# audio_dsp.net
KiCad netlist of a schematic drawn in Altium Designer
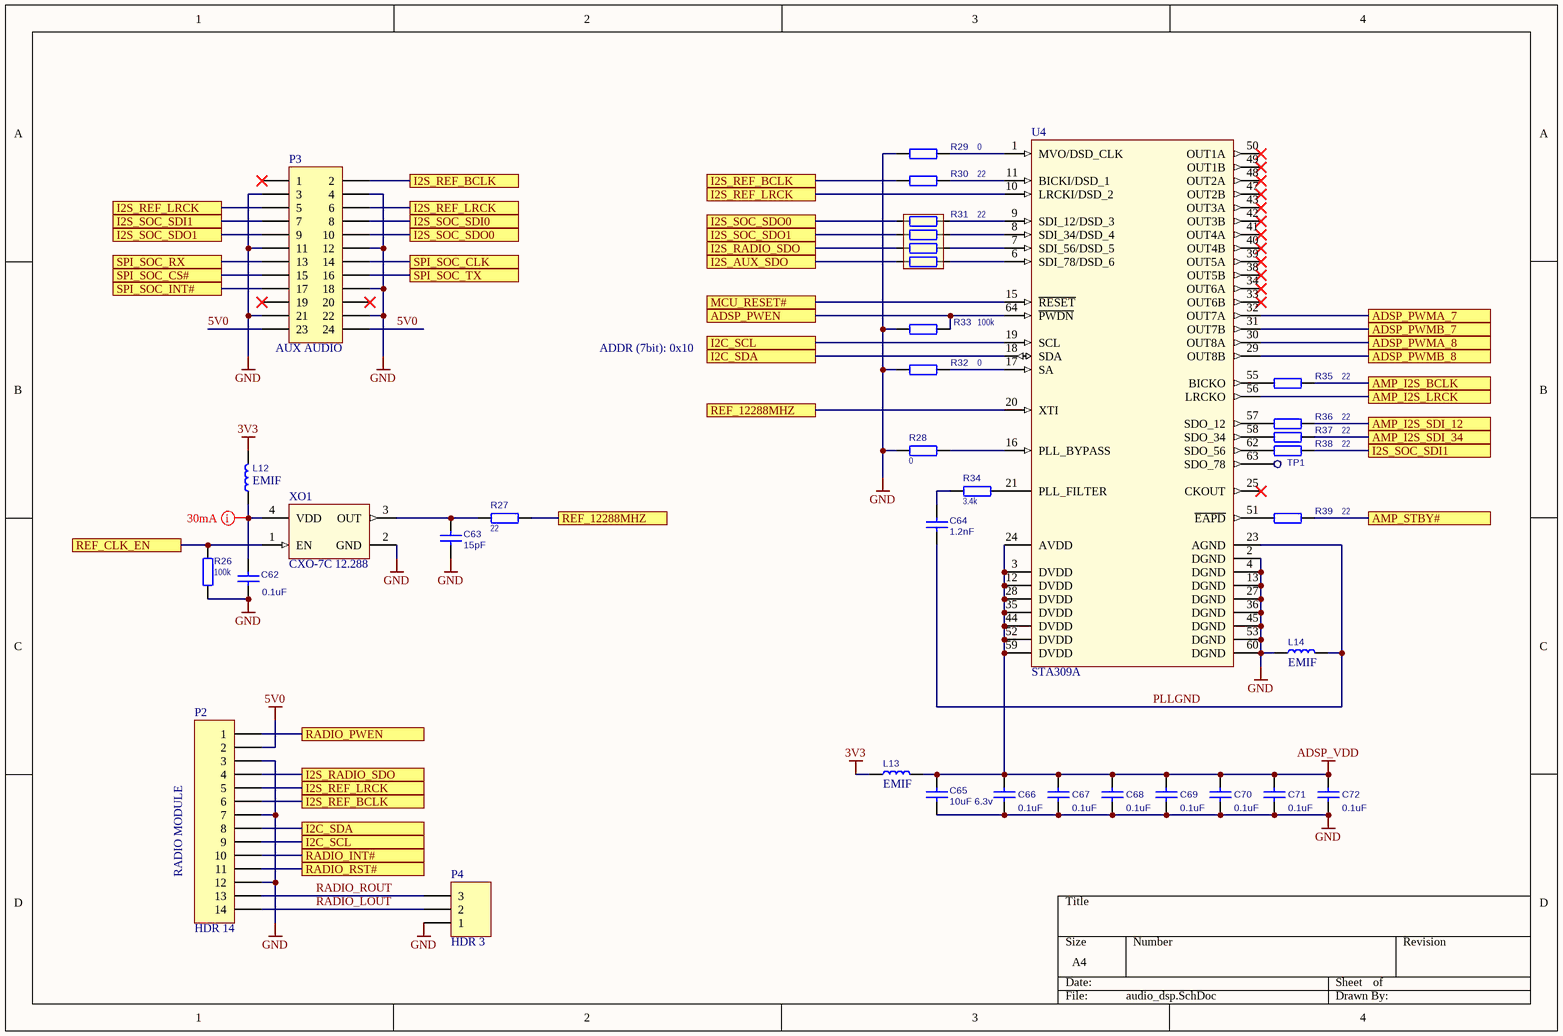
[diagram p0: audio_dsp.SchDoc]

(export (version "E")
  (design (tool "Eeschema 10.0.6"))
  (components
    (comp (ref "C62")
      (value "0.1uF")
      (footprint "Capacitors:C0603")
      (description "CAP_NPOL")
      (fields (field (name "Comment") "CC0603KRX7R9BB104"))
      (libsource (lib "capacitors") (part "CAP_NPOL"))
    )
    (comp (ref "C63")
      (value "15pF")
      (footprint "C0603")
      (description "CAP_NPOL")
      (fields (field (name "Comment") "CC0603GRNPO9BN150"))
      (libsource (lib "capacitors") (part "CAP_NPOL"))
    )
    (comp (ref "C64")
      (value "1.2nF")
      (footprint "Capacitors:C0603")
      (description "CAP_NPOL")
      (fields (field (name "Comment") "GRM1885C1H122JA01D"))
      (libsource (lib "capacitors") (part "CAP_NPOL"))
    )
    (comp (ref "C65")
      (value "10uF 6.3v")
      (footprint "Capacitors:C0603")
      (description "CAP_NPOL")
      (fields (field (name "Comment") "CC0603MRX5R5BB106"))
      (libsource (lib "capacitors") (part "CAP_NPOL"))
    )
    (comp (ref "C66")
      (value "0.1uF")
      (footprint "Capacitors:C0603")
      (description "CAP_NPOL")
      (fields (field (name "Comment") "CC0603KRX7R9BB104"))
      (libsource (lib "capacitors") (part "CAP_NPOL"))
    )
    (comp (ref "C67")
      (value "0.1uF")
      (footprint "Capacitors:C0603")
      (description "CAP_NPOL")
      (fields (field (name "Comment") "CC0603KRX7R9BB104"))
      (libsource (lib "capacitors") (part "CAP_NPOL"))
    )
    (comp (ref "C68")
      (value "0.1uF")
      (footprint "Capacitors:C0603")
      (description "CAP_NPOL")
      (fields (field (name "Comment") "CC0603KRX7R9BB104"))
      (libsource (lib "capacitors") (part "CAP_NPOL"))
    )
    (comp (ref "C69")
      (value "0.1uF")
      (footprint "Capacitors:C0603")
      (description "CAP_NPOL")
      (fields (field (name "Comment") "CC0603KRX7R9BB104"))
      (libsource (lib "capacitors") (part "CAP_NPOL"))
    )
    (comp (ref "C70")
      (value "0.1uF")
      (footprint "Capacitors:C0603")
      (description "CAP_NPOL")
      (fields (field (name "Comment") "CC0603KRX7R9BB104"))
      (libsource (lib "capacitors") (part "CAP_NPOL"))
    )
    (comp (ref "C71")
      (value "0.1uF")
      (footprint "Capacitors:C0603")
      (description "CAP_NPOL")
      (fields (field (name "Comment") "CC0603KRX7R9BB104"))
      (libsource (lib "capacitors") (part "CAP_NPOL"))
    )
    (comp (ref "C72")
      (value "0.1uF")
      (footprint "Capacitors:C0603")
      (description "CAP_NPOL")
      (fields (field (name "Comment") "CC0603KRX7R9BB104"))
      (libsource (lib "capacitors") (part "CAP_NPOL"))
    )
    (comp (ref "L12")
      (value "EMIF")
      (footprint "IND0603")
      (description "IND_WO_IRON")
      (fields (field (name "Comment") "BLM18AG102SN1D"))
      (libsource (lib "inductors") (part "IND_WO_IRON"))
    )
    (comp (ref "L13")
      (value "EMIF")
      (footprint "IND0603")
      (description "IND_WO_IRON")
      (fields (field (name "Comment") "BLM18AG102SN1D"))
      (libsource (lib "inductors") (part "IND_WO_IRON"))
    )
    (comp (ref "L14")
      (value "EMIF")
      (footprint "IND0603")
      (description "IND_WO_IRON")
      (fields (field (name "Comment") "BLM18AG102SN1D"))
      (libsource (lib "inductors") (part "IND_WO_IRON"))
    )
    (comp (ref "P2")
      (value "HDR 14")
      (footprint "PLS-14")
      (description "Header, 14-Pin")
      (fields (field (name "PUBLISHER") "Altium Limited"))
      (libsource (lib "HDR") (part "HDR 14"))
    )
    (comp (ref "P3")
      (value "AUX AUDIO")
      (footprint "PLD-12")
      (description "Header, 12-Pin, Dual row")
      (fields (field (name "PUBLISHER") "Altium Limited"))
      (libsource (lib "HDR") (part "HDR 12X2"))
    )
    (comp (ref "P4")
      (value "HDR 3")
      (footprint "PLS-3")
      (description "Header, 3-Pin")
      (fields (field (name "PUBLISHER") "Altium Limited"))
      (libsource (lib "HDR") (part "HDR 3"))
    )
    (comp (ref "R26")
      (value "100k")
      (footprint "R0603")
      (description "RES")
      (fields (field (name "Comment") "47k"))
      (libsource (lib "resistors") (part "RESISTOR"))
    )
    (comp (ref "R27")
      (value "22")
      (footprint "R0603")
      (description "RES")
      (libsource (lib "resistors") (part "RESISTOR"))
    )
    (comp (ref "R28")
      (value "0")
      (footprint "R0603")
      (description "RES")
      (libsource (lib "resistors") (part "RESISTOR"))
    )
    (comp (ref "R29")
      (value "0")
      (footprint "R0603")
      (description "RES")
      (libsource (lib "resistors") (part "RESISTOR"))
    )
    (comp (ref "R30")
      (value "22")
      (footprint "R0603")
      (description "RES")
      (libsource (lib "resistors") (part "RESISTOR"))
    )
    (comp (ref "R31")
      (value "22")
      (footprint "Resistors:R0804X4")
      (description "ARRAY")
      (fields (field (name "Comment") "TC124-JR-0722RL"))
      (libsource (lib "resistors") (part "ARRAY"))
    )
    (comp (ref "R32")
      (value "0")
      (footprint "R0603")
      (description "RES")
      (libsource (lib "resistors") (part "RESISTOR"))
    )
    (comp (ref "R33")
      (value "100k")
      (footprint "R0603")
      (description "RES")
      (libsource (lib "resistors") (part "RESISTOR"))
    )
    (comp (ref "R34")
      (value "3.4k")
      (footprint "R0603")
      (description "RES")
      (libsource (lib "resistors") (part "RESISTOR"))
    )
    (comp (ref "R35")
      (value "22")
      (footprint "R0603")
      (description "RES")
      (libsource (lib "resistors") (part "RESISTOR"))
    )
    (comp (ref "R36")
      (value "22")
      (footprint "R0603")
      (description "RES")
      (libsource (lib "resistors") (part "RESISTOR"))
    )
    (comp (ref "R37")
      (value "22")
      (footprint "R0603")
      (description "RES")
      (libsource (lib "resistors") (part "RESISTOR"))
    )
    (comp (ref "R38")
      (value "22")
      (footprint "R0603")
      (description "RES")
      (libsource (lib "resistors") (part "RESISTOR"))
    )
    (comp (ref "R39")
      (value "22")
      (footprint "R0603")
      (description "RES")
      (libsource (lib "resistors") (part "RESISTOR"))
    )
    (comp (ref "TP1")
      (value "TEST-POINT")
      (footprint "PAD")
      (description "PCB terminal block")
      (libsource (lib "TestPoint") (part "TEST-POINT"))
    )
    (comp (ref "U4")
      (value "STA309A")
      (footprint "PM064_N")
      (description "Multi-channel digital audio processor with DDX®")
      (libsource (lib "STA309A") (part "STA309A"))
    )
    (comp (ref "XO1") (value "CXO-7C 12.288") (footprint "CXO-5032") (libsource (lib "xtal") (part "CXO-7C")))
  )
  (nets
    (net (code "1") (name "/ADSP_PWEN") (class "Default")
      (node (ref "R33") (pin "1") (pinfunction "1_1") (pintype "passive"))
      (node (ref "U4") (pin "64") (pinfunction "~{PWDN}_64") (pintype "input"))
    )
    (net (code "2") (name "/ADSP_PWMA_7") (class "Default")
      (node (ref "U4") (pin "32") (pinfunction "OUT7A_32") (pintype "output"))
    )
    (net (code "3") (name "/ADSP_PWMA_8") (class "Default")
      (node (ref "U4") (pin "30") (pinfunction "OUT8A_30") (pintype "output"))
    )
    (net (code "4") (name "/ADSP_PWMB_7") (class "Default")
      (node (ref "U4") (pin "31") (pinfunction "OUT7B_31") (pintype "output"))
    )
    (net (code "5") (name "/ADSP_PWMB_8") (class "Default")
      (node (ref "U4") (pin "29") (pinfunction "OUT8B_29") (pintype "output"))
    )
    (net (code "6") (name "/AMP_I2S_BCLK") (class "Default")
      (node (ref "R35") (pin "2") (pinfunction "2_2") (pintype "passive"))
    )
    (net (code "7") (name "/AMP_I2S_LRCK") (class "Default")
      (node (ref "U4") (pin "56") (pinfunction "LRCKO_56") (pintype "output"))
    )
    (net (code "8") (name "/AMP_I2S_SDI_12") (class "Default")
      (node (ref "R36") (pin "2") (pinfunction "2_2") (pintype "passive"))
    )
    (net (code "9") (name "/AMP_I2S_SDI_34") (class "Default")
      (node (ref "R37") (pin "2") (pinfunction "2_2") (pintype "passive"))
    )
    (net (code "10") (name "/AMP_STBY#") (class "Default")
      (node (ref "R39") (pin "2") (pinfunction "2_2") (pintype "passive"))
    )
    (net (code "11") (name "/I2C_SCL") (class "Default")
      (node (ref "P2") (pin "9") (pinfunction "9_9") (pintype "passive"))
      (node (ref "U4") (pin "19") (pinfunction "SCL_19") (pintype "input"))
    )
    (net (code "12") (name "/I2C_SDA") (class "Default")
      (node (ref "P2") (pin "8") (pinfunction "8_8") (pintype "passive"))
      (node (ref "U4") (pin "18") (pinfunction "SDA_18") (pintype "bidirectional"))
    )
    (net (code "13") (name "/I2S_AUX_SDO") (class "Default")
      (node (ref "R31") (pin "1") (pinfunction "1_1") (pintype "passive"))
    )
    (net (code "14") (name "/I2S_RADIO_SDO") (class "Default")
      (node (ref "P2") (pin "4") (pinfunction "4_4") (pintype "passive"))
      (node (ref "R31") (pin "3") (pinfunction "3_3") (pintype "passive"))
    )
    (net (code "15") (name "/I2S_REF_BCLK") (class "Default")
      (node (ref "P2") (pin "6") (pinfunction "6_6") (pintype "passive"))
      (node (ref "P3") (pin "2") (pinfunction "2_2") (pintype "passive"))
      (node (ref "R30") (pin "1") (pinfunction "1_1") (pintype "passive"))
    )
    (net (code "16") (name "/I2S_REF_LRCK") (class "Default")
      (node (ref "P2") (pin "5") (pinfunction "5_5") (pintype "passive"))
      (node (ref "P3") (pin "5") (pinfunction "5_5") (pintype "passive"))
      (node (ref "P3") (pin "6") (pinfunction "6_6") (pintype "passive"))
      (node (ref "U4") (pin "10") (pinfunction "LRCKI/DSD_2_10") (pintype "input"))
    )
    (net (code "17") (name "/I2S_SOC_SDI0") (class "Default")
      (node (ref "P3") (pin "8") (pinfunction "8_8") (pintype "passive"))
    )
    (net (code "18") (name "/I2S_SOC_SDI1") (class "Default")
      (node (ref "P3") (pin "7") (pinfunction "7_7") (pintype "passive"))
      (node (ref "R38") (pin "2") (pinfunction "2_2") (pintype "passive"))
    )
    (net (code "19") (name "/I2S_SOC_SDO0") (class "Default")
      (node (ref "P3") (pin "10") (pinfunction "10_10") (pintype "passive"))
      (node (ref "R31") (pin "7") (pinfunction "7_7") (pintype "passive"))
    )
    (net (code "20") (name "/I2S_SOC_SDO1") (class "Default")
      (node (ref "P3") (pin "9") (pinfunction "9_9") (pintype "passive"))
      (node (ref "R31") (pin "5") (pinfunction "5_5") (pintype "passive"))
    )
    (net (code "21") (name "/MCU_RESET#") (class "Default")
      (node (ref "U4") (pin "15") (pinfunction "~{RESET}_15") (pintype "input"))
    )
    (net (code "22") (name "/PLLGND") (class "Default")
      (node (ref "C64") (pin "2") (pinfunction "2_2") (pintype "passive"))
      (node (ref "L14") (pin "1") (pintype "passive"))
      (node (ref "U4") (pin "23") (pinfunction "AGND_23") (pintype "power_in"))
    )
    (net (code "23") (name "/RADIO_INT#") (class "Default")
      (node (ref "P2") (pin "10") (pinfunction "10_10") (pintype "passive"))
    )
    (net (code "24") (name "/RADIO_LOUT") (class "Default")
      (node (ref "P2") (pin "14") (pinfunction "14_14") (pintype "passive"))
      (node (ref "P4") (pin "2") (pinfunction "2_2") (pintype "passive"))
    )
    (net (code "25") (name "/RADIO_PWEN") (class "Default")
      (node (ref "P2") (pin "1") (pinfunction "1_1") (pintype "passive"))
    )
    (net (code "26") (name "/RADIO_ROUT") (class "Default")
      (node (ref "P2") (pin "13") (pinfunction "13_13") (pintype "passive"))
      (node (ref "P4") (pin "3") (pinfunction "3_3") (pintype "passive"))
    )
    (net (code "27") (name "/RADIO_RST#") (class "Default")
      (node (ref "P2") (pin "11") (pinfunction "11_11") (pintype "passive"))
    )
    (net (code "28") (name "/REF_12288MHZ") (class "Default")
      (node (ref "R27") (pin "1") (pinfunction "1_1") (pintype "passive"))
      (node (ref "U4") (pin "20") (pinfunction "XTI_20") (pintype "input"))
    )
    (net (code "29") (name "/REF_CLK_EN") (class "Default")
      (node (ref "R26") (pin "1") (pinfunction "1_1") (pintype "passive"))
      (node (ref "XO1") (pin "1") (pinfunction "EN_1") (pintype "input"))
    )
    (net (code "30") (name "/SPI_SOC_CLK") (class "Default")
      (node (ref "P3") (pin "14") (pinfunction "14_14") (pintype "passive"))
    )
    (net (code "31") (name "/SPI_SOC_CS#") (class "Default")
      (node (ref "P3") (pin "15") (pinfunction "15_15") (pintype "passive"))
    )
    (net (code "32") (name "/SPI_SOC_INT#") (class "Default")
      (node (ref "P3") (pin "17") (pinfunction "17_17") (pintype "passive"))
    )
    (net (code "33") (name "/SPI_SOC_RX") (class "Default")
      (node (ref "P3") (pin "13") (pinfunction "13_13") (pintype "passive"))
    )
    (net (code "34") (name "/SPI_SOC_TX") (class "Default")
      (node (ref "P3") (pin "16") (pinfunction "16_16") (pintype "passive"))
    )
    (net (code "35") (name "3V3") (class "Default")
      (node (ref "L12") (pin "1") (pintype "passive"))
      (node (ref "L13") (pin "2") (pintype "passive"))
    )
    (net (code "36") (name "5V0") (class "Default")
      (node (ref "P2") (pin "2") (pinfunction "2_2") (pintype "passive"))
      (node (ref "P3") (pin "23") (pinfunction "23_23") (pintype "passive"))
      (node (ref "P3") (pin "24") (pinfunction "24_24") (pintype "passive"))
    )
    (net (code "37") (name "ADSP_VDD") (class "Default")
      (node (ref "C65") (pin "2") (pinfunction "2_2") (pintype "passive"))
      (node (ref "C66") (pin "1") (pinfunction "1_1") (pintype "passive"))
      (node (ref "C67") (pin "1") (pinfunction "1_1") (pintype "passive"))
      (node (ref "C68") (pin "1") (pinfunction "1_1") (pintype "passive"))
      (node (ref "C69") (pin "1") (pinfunction "1_1") (pintype "passive"))
      (node (ref "C70") (pin "1") (pinfunction "1_1") (pintype "passive"))
      (node (ref "C71") (pin "1") (pinfunction "1_1") (pintype "passive"))
      (node (ref "C72") (pin "1") (pinfunction "1_1") (pintype "passive"))
      (node (ref "L13") (pin "1") (pintype "passive"))
      (node (ref "U4") (pin "12") (pinfunction "DVDD_12") (pintype "power_in"))
      (node (ref "U4") (pin "24") (pinfunction "AVDD_24") (pintype "power_in"))
      (node (ref "U4") (pin "28") (pinfunction "DVDD_28") (pintype "power_in"))
      (node (ref "U4") (pin "3") (pinfunction "DVDD_3") (pintype "power_in"))
      (node (ref "U4") (pin "35") (pinfunction "DVDD_35") (pintype "power_in"))
      (node (ref "U4") (pin "44") (pinfunction "DVDD_44") (pintype "power_in"))
      (node (ref "U4") (pin "52") (pinfunction "DVDD_52") (pintype "passive"))
      (node (ref "U4") (pin "59") (pinfunction "DVDD_59") (pintype "passive"))
    )
    (net (code "38") (name "GND") (class "Default")
      (node (ref "C62") (pin "1") (pinfunction "1_1") (pintype "passive"))
      (node (ref "C63") (pin "2") (pinfunction "2_2") (pintype "passive"))
      (node (ref "C65") (pin "1") (pinfunction "1_1") (pintype "passive"))
      (node (ref "C66") (pin "2") (pinfunction "2_2") (pintype "passive"))
      (node (ref "C67") (pin "2") (pinfunction "2_2") (pintype "passive"))
      (node (ref "C68") (pin "2") (pinfunction "2_2") (pintype "passive"))
      (node (ref "C69") (pin "2") (pinfunction "2_2") (pintype "passive"))
      (node (ref "C70") (pin "2") (pinfunction "2_2") (pintype "passive"))
      (node (ref "C71") (pin "2") (pinfunction "2_2") (pintype "passive"))
      (node (ref "C72") (pin "2") (pinfunction "2_2") (pintype "passive"))
      (node (ref "L14") (pin "2") (pintype "passive"))
      (node (ref "P2") (pin "12") (pinfunction "12_12") (pintype "passive"))
      (node (ref "P2") (pin "3") (pinfunction "3_3") (pintype "passive"))
      (node (ref "P2") (pin "7") (pinfunction "7_7") (pintype "passive"))
      (node (ref "P3") (pin "11") (pinfunction "11_11") (pintype "passive"))
      (node (ref "P3") (pin "12") (pinfunction "12_12") (pintype "passive"))
      (node (ref "P3") (pin "18") (pinfunction "18_18") (pintype "passive"))
      (node (ref "P3") (pin "21") (pinfunction "21_21") (pintype "passive"))
      (node (ref "P3") (pin "22") (pinfunction "22_22") (pintype "passive"))
      (node (ref "P3") (pin "3") (pinfunction "3_3") (pintype "passive"))
      (node (ref "P3") (pin "4") (pinfunction "4_4") (pintype "passive"))
      (node (ref "P4") (pin "1") (pinfunction "1_1") (pintype "passive"))
      (node (ref "R26") (pin "2") (pinfunction "2_2") (pintype "passive"))
      (node (ref "R28") (pin "1") (pinfunction "1_1") (pintype "passive"))
      (node (ref "R29") (pin "1") (pinfunction "1_1") (pintype "passive"))
      (node (ref "R32") (pin "1") (pinfunction "1_1") (pintype "passive"))
      (node (ref "R33") (pin "2") (pinfunction "2_2") (pintype "passive"))
      (node (ref "U4") (pin "13") (pinfunction "DGND_13") (pintype "power_in"))
      (node (ref "U4") (pin "2") (pinfunction "DGND_2") (pintype "power_in"))
      (node (ref "U4") (pin "27") (pinfunction "DGND_27") (pintype "power_in"))
      (node (ref "U4") (pin "36") (pinfunction "DGND_36") (pintype "passive"))
      (node (ref "U4") (pin "4") (pinfunction "DGND_4") (pintype "power_in"))
      (node (ref "U4") (pin "45") (pinfunction "DGND_45") (pintype "power_in"))
      (node (ref "U4") (pin "53") (pinfunction "DGND_53") (pintype "power_in"))
      (node (ref "U4") (pin "60") (pinfunction "DGND_60") (pintype "power_in"))
      (node (ref "XO1") (pin "2") (pinfunction "GND_2") (pintype "power_in"))
    )
    (net (code "39") (name "Net-(C64-Pad1)") (class "Default")
      (node (ref "C64") (pin "1") (pinfunction "1_1") (pintype "passive"))
      (node (ref "R34") (pin "2") (pinfunction "2_2") (pintype "passive"))
    )
    (net (code "40") (name "Net-(U4-BICKI{slash}DSD_1)") (class "Default")
      (node (ref "R30") (pin "2") (pinfunction "2_2") (pintype "passive"))
      (node (ref "U4") (pin "11") (pinfunction "BICKI/DSD_1_11") (pintype "input"))
    )
    (net (code "41") (name "Net-(U4-BICKO)") (class "Default")
      (node (ref "R35") (pin "1") (pinfunction "1_1") (pintype "passive"))
      (node (ref "U4") (pin "55") (pinfunction "BICKO_55") (pintype "output"))
    )
    (net (code "42") (name "Net-(U4-MVO{slash}DSD_CLK)") (class "Default")
      (node (ref "R29") (pin "2") (pinfunction "2_2") (pintype "passive"))
      (node (ref "U4") (pin "1") (pinfunction "MVO/DSD_CLK_1") (pintype "input"))
    )
    (net (code "43") (name "Net-(U4-PLL_BYPASS)") (class "Default")
      (node (ref "R28") (pin "2") (pinfunction "2_2") (pintype "passive"))
      (node (ref "U4") (pin "16") (pinfunction "PLL_BYPASS_16") (pintype "input"))
    )
    (net (code "44") (name "Net-(U4-PLL_FILTER)") (class "Default")
      (node (ref "R34") (pin "1") (pinfunction "1_1") (pintype "passive"))
      (node (ref "U4") (pin "21") (pinfunction "PLL_FILTER_21") (pintype "passive"))
    )
    (net (code "45") (name "Net-(U4-SA)") (class "Default")
      (node (ref "R32") (pin "2") (pinfunction "2_2") (pintype "passive"))
      (node (ref "U4") (pin "17") (pinfunction "SA_17") (pintype "input"))
    )
    (net (code "46") (name "Net-(U4-SDI_12{slash}DSD_3)") (class "Default")
      (node (ref "R31") (pin "8") (pinfunction "8_8") (pintype "passive"))
      (node (ref "U4") (pin "9") (pinfunction "SDI_12/DSD_3_9") (pintype "input"))
    )
    (net (code "47") (name "Net-(U4-SDI_34{slash}DSD_4)") (class "Default")
      (node (ref "R31") (pin "6") (pinfunction "6_6") (pintype "passive"))
      (node (ref "U4") (pin "8") (pinfunction "SDI_34/DSD_4_8") (pintype "input"))
    )
    (net (code "48") (name "Net-(U4-SDI_56{slash}DSD_5)") (class "Default")
      (node (ref "R31") (pin "4") (pinfunction "4_4") (pintype "passive"))
      (node (ref "U4") (pin "7") (pinfunction "SDI_56/DSD_5_7") (pintype "input"))
    )
    (net (code "49") (name "Net-(U4-SDI_78{slash}DSD_6)") (class "Default")
      (node (ref "R31") (pin "2") (pinfunction "2_2") (pintype "passive"))
      (node (ref "U4") (pin "6") (pinfunction "SDI_78/DSD_6_6") (pintype "input"))
    )
    (net (code "50") (name "Net-(U4-SDO_12)") (class "Default")
      (node (ref "R36") (pin "1") (pinfunction "1_1") (pintype "passive"))
      (node (ref "U4") (pin "57") (pinfunction "SDO_12_57") (pintype "output"))
    )
    (net (code "51") (name "Net-(U4-SDO_34)") (class "Default")
      (node (ref "R37") (pin "1") (pinfunction "1_1") (pintype "passive"))
      (node (ref "U4") (pin "58") (pinfunction "SDO_34_58") (pintype "output"))
    )
    (net (code "52") (name "Net-(U4-SDO_56)") (class "Default")
      (node (ref "R38") (pin "1") (pinfunction "1_1") (pintype "passive"))
      (node (ref "U4") (pin "62") (pinfunction "SDO_56_62") (pintype "output"))
    )
    (net (code "53") (name "Net-(U4-SDO_78)") (class "Default")
      (node (ref "TP1") (pin "1") (pinfunction "1_1") (pintype "passive"))
      (node (ref "U4") (pin "63") (pinfunction "SDO_78_63") (pintype "output"))
    )
    (net (code "54") (name "Net-(U4-~{EAPD})") (class "Default")
      (node (ref "R39") (pin "1") (pinfunction "1_1") (pintype "passive"))
      (node (ref "U4") (pin "51") (pinfunction "~{EAPD}_51") (pintype "output"))
    )
    (net (code "55") (name "Net-(XO1-OUT)") (class "Default")
      (node (ref "C63") (pin "1") (pinfunction "1_1") (pintype "passive"))
      (node (ref "R27") (pin "2") (pinfunction "2_2") (pintype "passive"))
      (node (ref "XO1") (pin "3") (pinfunction "OUT_3") (pintype "output"))
    )
    (net (code "56") (name "Net-(XO1-VDD)") (class "Default")
      (node (ref "C62") (pin "2") (pinfunction "2_2") (pintype "passive"))
      (node (ref "L12") (pin "2") (pintype "passive"))
      (node (ref "XO1") (pin "4") (pinfunction "VDD_4") (pintype "power_in"))
    )
    (net (code "57") (name "unconnected-(P3-Pad1)") (class "Default")
      (node (ref "P3") (pin "1") (pinfunction "1_1") (pintype "passive+no_connect"))
    )
    (net (code "58") (name "unconnected-(P3-Pad19)") (class "Default")
      (node (ref "P3") (pin "19") (pinfunction "19_19") (pintype "passive+no_connect"))
    )
    (net (code "59") (name "unconnected-(P3-Pad20)") (class "Default")
      (node (ref "P3") (pin "20") (pinfunction "20_20") (pintype "passive+no_connect"))
    )
    (net (code "60") (name "unconnected-(U4-CKOUT-Pad25)") (class "Default")
      (node (ref "U4") (pin "25") (pinfunction "CKOUT_25") (pintype "output+no_connect"))
    )
    (net (code "61") (name "unconnected-(U4-OUT1A-Pad50)") (class "Default")
      (node (ref "U4") (pin "50") (pinfunction "OUT1A_50") (pintype "output+no_connect"))
    )
    (net (code "62") (name "unconnected-(U4-OUT1B-Pad49)") (class "Default")
      (node (ref "U4") (pin "49") (pinfunction "OUT1B_49") (pintype "output+no_connect"))
    )
    (net (code "63") (name "unconnected-(U4-OUT2A-Pad48)") (class "Default")
      (node (ref "U4") (pin "48") (pinfunction "OUT2A_48") (pintype "output+no_connect"))
    )
    (net (code "64") (name "unconnected-(U4-OUT2B-Pad47)") (class "Default")
      (node (ref "U4") (pin "47") (pinfunction "OUT2B_47") (pintype "output+no_connect"))
    )
    (net (code "65") (name "unconnected-(U4-OUT3A-Pad43)") (class "Default")
      (node (ref "U4") (pin "43") (pinfunction "OUT3A_43") (pintype "output+no_connect"))
    )
    (net (code "66") (name "unconnected-(U4-OUT3B-Pad42)") (class "Default")
      (node (ref "U4") (pin "42") (pinfunction "OUT3B_42") (pintype "output+no_connect"))
    )
    (net (code "67") (name "unconnected-(U4-OUT4A-Pad41)") (class "Default")
      (node (ref "U4") (pin "41") (pinfunction "OUT4A_41") (pintype "output+no_connect"))
    )
    (net (code "68") (name "unconnected-(U4-OUT4B-Pad40)") (class "Default")
      (node (ref "U4") (pin "40") (pinfunction "OUT4B_40") (pintype "output+no_connect"))
    )
    (net (code "69") (name "unconnected-(U4-OUT5A-Pad39)") (class "Default")
      (node (ref "U4") (pin "39") (pinfunction "OUT5A_39") (pintype "output+no_connect"))
    )
    (net (code "70") (name "unconnected-(U4-OUT5B-Pad38)") (class "Default")
      (node (ref "U4") (pin "38") (pinfunction "OUT5B_38") (pintype "output+no_connect"))
    )
    (net (code "71") (name "unconnected-(U4-OUT6A-Pad34)") (class "Default")
      (node (ref "U4") (pin "34") (pinfunction "OUT6A_34") (pintype "output+no_connect"))
    )
    (net (code "72") (name "unconnected-(U4-OUT6B-Pad33)") (class "Default")
      (node (ref "U4") (pin "33") (pinfunction "OUT6B_33") (pintype "output+no_connect"))
    )
  )
)
